# midterm.net
KiCad netlist of a schematic drawn in EAGLE
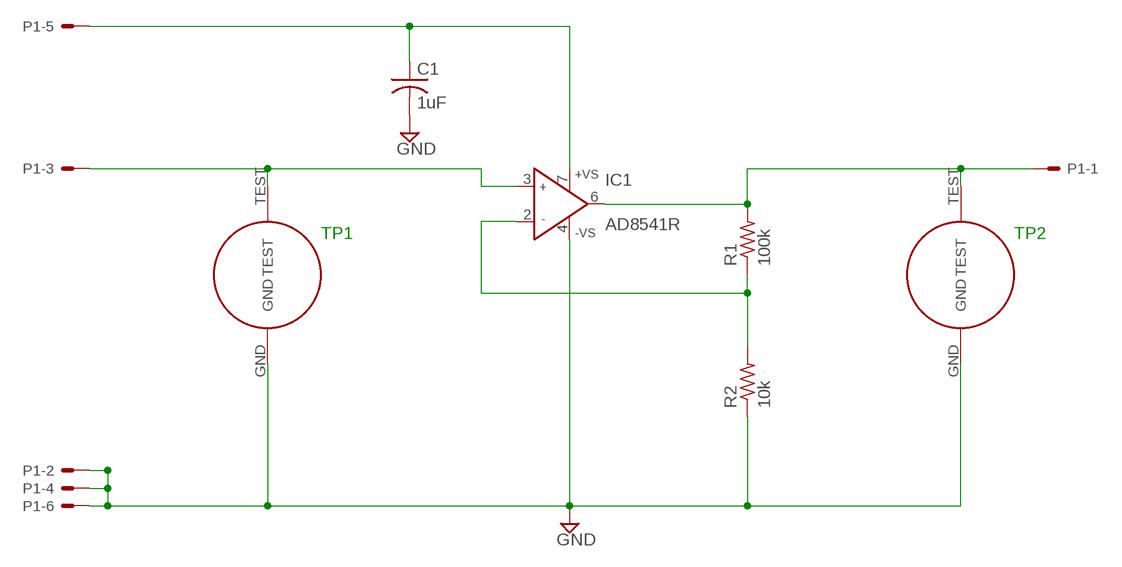
[diagram p0: schematic, sheet 1]

(export (version "E")
  (design (tool "Eeschema 10.0.6"))
  (components
    (comp (ref "C1")
      (value "1uF")
      (footprint "eagle-import:C1206")
      (libsource (lib "eagle-import") (part "C-USC1206"))
    )
    (comp (ref "IC1")
      (value "AD8541R")
      (footprint "eagle-import:SO8")
      (fields (field (name "MPN") "AD8541ARZ"))
      (libsource (lib "eagle-import") (part "AD8541R"))
    )
    (comp (ref "P1")
      (value "22-23-2061")
      (footprint "eagle-import:22-23-2061")
      (fields (field (name "MF") "MOLEX"))
      (libsource (lib "eagle-import") (part "22-23-2061"))
    )
    (comp (ref "R1")
      (value "100k")
      (footprint "eagle-import:M2012")
      (libsource (lib "eagle-import") (part "R-US_M2012"))
    )
    (comp (ref "R2")
      (value "10k")
      (footprint "eagle-import:M2012")
      (libsource (lib "eagle-import") (part "R-US_M2012"))
    )
    (comp (ref "TP1")
      (value "TEST_POINT")
      (footprint "eagle-import:TEST_POINT")
      (libsource (lib "eagle-import") (part "TEST_POINT"))
    )
    (comp (ref "TP2")
      (value "TEST_POINT")
      (footprint "eagle-import:TEST_POINT")
      (libsource (lib "eagle-import") (part "TEST_POINT"))
    )
  )
  (nets
    (net (code "1") (name "GND") (class "Default")
      (node (ref "C1") (pin "2") (pinfunction "2_2") (pintype "passive"))
      (node (ref "IC1") (pin "4") (pinfunction "-VS_4") (pintype "input"))
      (node (ref "P1") (pin "2") (pinfunction "S_2") (pintype "passive"))
      (node (ref "P1") (pin "4") (pinfunction "S_4") (pintype "passive"))
      (node (ref "P1") (pin "6") (pinfunction "S_6") (pintype "passive"))
      (node (ref "R2") (pin "1") (pinfunction "1_1") (pintype "passive"))
      (node (ref "TP1") (pin "GND") (pinfunction "GND_GND") (pintype "bidirectional"))
      (node (ref "TP2") (pin "GND") (pinfunction "GND_GND") (pintype "bidirectional"))
    )
    (net (code "2") (name "Net-(IC1-+VS)") (class "Default")
      (node (ref "C1") (pin "1") (pinfunction "1_1") (pintype "passive"))
      (node (ref "IC1") (pin "7") (pinfunction "+VS_7") (pintype "input"))
      (node (ref "P1") (pin "5") (pinfunction "S_5") (pintype "passive"))
    )
    (net (code "3") (name "Net-(IC1-IN+)") (class "Default")
      (node (ref "IC1") (pin "3") (pinfunction "IN+_3") (pintype "input"))
      (node (ref "P1") (pin "3") (pinfunction "S_3") (pintype "passive"))
      (node (ref "TP1") (pin "TEST") (pinfunction "TEST_TEST") (pintype "bidirectional"))
    )
    (net (code "4") (name "Net-(IC1-IN-)") (class "Default")
      (node (ref "IC1") (pin "2") (pinfunction "IN-_2") (pintype "input"))
      (node (ref "R1") (pin "1") (pinfunction "1_1") (pintype "passive"))
      (node (ref "R2") (pin "2") (pinfunction "2_2") (pintype "passive"))
    )
    (net (code "5") (name "Net-(IC1-OUT)") (class "Default")
      (node (ref "IC1") (pin "6") (pinfunction "OUT_6") (pintype "output"))
      (node (ref "P1") (pin "1") (pinfunction "S_1") (pintype "passive"))
      (node (ref "R1") (pin "2") (pinfunction "2_2") (pintype "passive"))
      (node (ref "TP2") (pin "TEST") (pinfunction "TEST_TEST") (pintype "bidirectional"))
    )
  )
)
